# Micro.net
KiCad netlist of a schematic drawn in Altium Designer
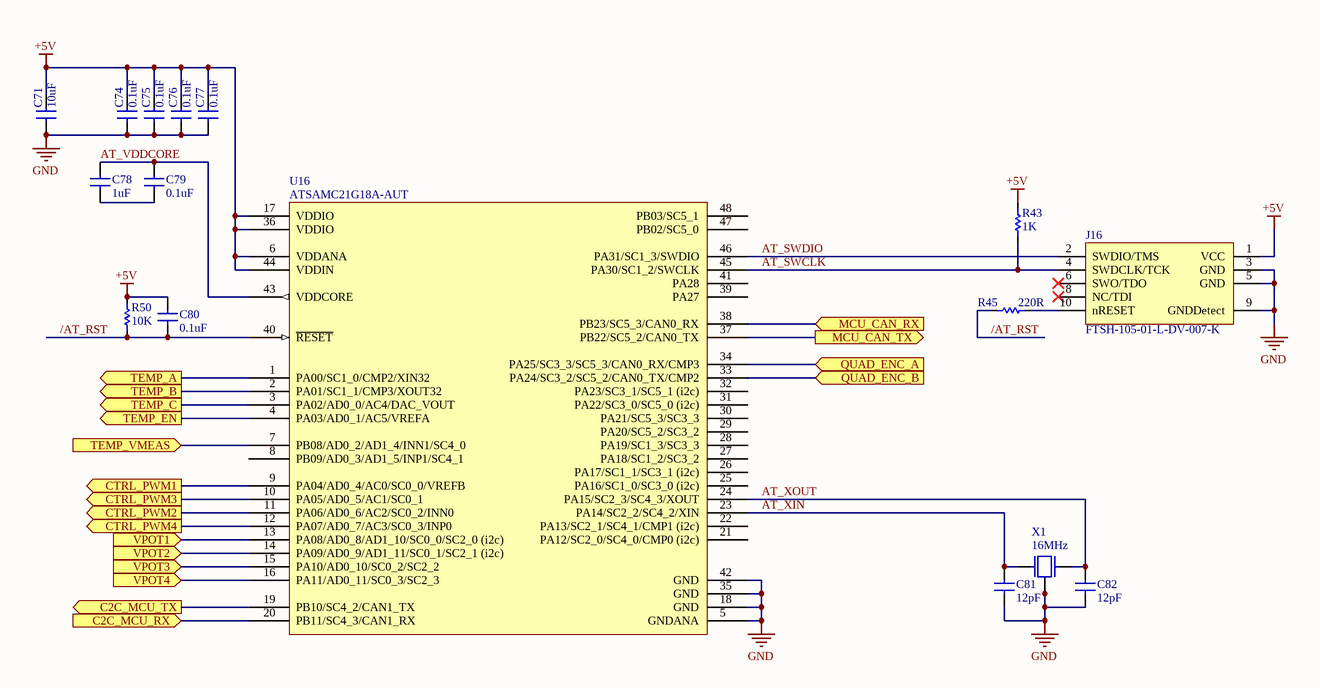
[diagram p0: Micro.SchDoc]

(export (version "E")
  (design (tool "Eeschema 10.0.6"))
  (components
    (comp (ref "C71")
      (value "10uF")
      (footprint "0603_Capacitor")
      (description "CAP CER 10UF 6.3V X5R 0603")
      (fields (field (name "VOLTAGE") "6.3V") (field (name "Comment") "CAP 10uF 6.3V X5R"))
      (libsource (lib "capacitor") (part "C_0603_10uF_6.3V_20%"))
    )
    (comp (ref "C74")
      (value "0.1uF")
      (footprint "0402_CAPACITOR")
      (description "CAP CERM 0.1uF 10% 16V 0402")
      (fields (field (name "VOLTAGE") "16V") (field (name "Comment") "CAP 0.1uF 16V X7R"))
      (libsource (lib "capacitor") (part "C_0402_0.1uF_16V_10%"))
    )
    (comp (ref "C75")
      (value "0.1uF")
      (footprint "0402_CAPACITOR")
      (description "CAP CERM 0.1uF 10% 16V 0402")
      (fields (field (name "VOLTAGE") "16V") (field (name "Comment") "CAP 0.1uF 16V X7R"))
      (libsource (lib "capacitor") (part "C_0402_0.1uF_16V_10%"))
    )
    (comp (ref "C76")
      (value "0.1uF")
      (footprint "0402_CAPACITOR")
      (description "CAP CERM 0.1uF 10% 16V 0402")
      (fields (field (name "VOLTAGE") "16V") (field (name "Comment") "CAP 0.1uF 16V X7R"))
      (libsource (lib "capacitor") (part "C_0402_0.1uF_16V_10%"))
    )
    (comp (ref "C77")
      (value "0.1uF")
      (footprint "0402_CAPACITOR")
      (description "CAP CERM 0.1uF 10% 16V 0402")
      (fields (field (name "VOLTAGE") "16V") (field (name "Comment") "CAP 0.1uF 16V X7R"))
      (libsource (lib "capacitor") (part "C_0402_0.1uF_16V_10%"))
    )
    (comp (ref "C78")
      (value "1uF")
      (footprint "0603_CAPACITOR")
      (description "CAP CERM 1uF 10% 16V 0603")
      (fields
        (field (name "VOLTAGE") "16V")
        (field (name "Comment") "CAP 1uF 16V X7R")
        (field (name "SVP CREATOR") "Spencer Berglund")
      )
      (libsource (lib "capacitor") (part "C_0603_1uF_16V_10%"))
    )
    (comp (ref "C79")
      (value "0.1uF")
      (footprint "0402_CAPACITOR")
      (description "CAP CERM 0.1uF 10% 16V 0402")
      (fields (field (name "VOLTAGE") "16V") (field (name "Comment") "CAP 0.1uF 16V X7R"))
      (libsource (lib "capacitor") (part "C_0402_0.1uF_16V_10%"))
    )
    (comp (ref "C80")
      (value "0.1uF")
      (footprint "0402_CAPACITOR")
      (description "CAP CERM 0.1uF 10% 16V 0402")
      (fields (field (name "VOLTAGE") "16V") (field (name "Comment") "CAP 0.1uF 16V X7R"))
      (libsource (lib "capacitor") (part "C_0402_0.1uF_16V_10%"))
    )
    (comp (ref "C81")
      (value "12pF")
      (footprint "0402_CAPACITOR")
      (fields
        (field (name "VOLTAGE") "50V")
        (field (name "MANUFACTURER") "Samsung")
        (field (name "MANUFACTURER PART NUMBER") "CL05CJB5NNNC")
      )
      (libsource (lib "capacitor") (part "C_0402_generic_C0G/NP0_50V_5%"))
    )
    (comp (ref "C82")
      (value "12pF")
      (footprint "0402_CAPACITOR")
      (fields
        (field (name "VOLTAGE") "50V")
        (field (name "MANUFACTURER") "Samsung")
        (field (name "MANUFACTURER PART NUMBER") "CL05CJB5NNNC")
      )
      (libsource (lib "capacitor") (part "C_0402_generic_C0G/NP0_50V_5%"))
    )
    (comp (ref "J16")
      (value "FTSH-105-01-L-DV-007-K")
      (footprint "J_Cortex_JTAG_SMD")
      (description "CORTEX JTAG DEBUG CONNECTOR")
      (fields (field (name "MANUFACTURER") "Samtec Inc"))
      (libsource (lib "connector") (part "J_Cortex_JTAG_SMD"))
    )
    (comp (ref "R43")
      (value "1K")
      (footprint "0402_Resistor")
      (description "Generic 0402 Resistor (10.2R to 10M)")
      (fields (field (name "TOLERANCE") "±1%") (field (name "MANUFACTURER") "Yageo"))
      (libsource (lib "resistor") (part "R_0402_generic_1%"))
    )
    (comp (ref "R45")
      (value "220R")
      (footprint "0402_Resistor")
      (description "Generic 0402 Resistor (10.2R to 10M)")
      (fields (field (name "TOLERANCE") "±1%") (field (name "MANUFACTURER") "Yageo"))
      (libsource (lib "resistor") (part "R_0402_generic_1%"))
    )
    (comp (ref "R50")
      (value "10K")
      (footprint "0402_Resistor")
      (description "Generic 0402 Resistor (10.2R to 10M)")
      (fields (field (name "TOLERANCE") "±1%") (field (name "MANUFACTURER") "Yageo"))
      (libsource (lib "resistor") (part "R_0402_generic_1%"))
    )
    (comp (ref "U16")
      (value "ATSAMC21G18A-AUT")
      (footprint "TQFP-48")
      (description "ARM® Cortex®-M0+ SAM C21 Microcontroller IC 32-Bit 48MHz 256KB (256K x 8) FLASH 48-TQFP (7x7)")
      (libsource (lib "ic") (part "U_ATSAMC21G18A-AUT"))
    )
    (comp (ref "X1")
      (value "16MHz")
      (footprint "X_TSX-3225")
      (description "16MHz ±10ppm Crystal 9pF 60 Ohms 4-SMD, No Lead")
      (fields
        (field (name "MANUFACTURER") "Epson")
        (field (name "MANUFACTURER PART NUMBER") "TSX-322516.0000MF18X-AC3")
      )
      (libsource (lib "misc") (part "X_TSX-3225_16.0000MF18X"))
    )
  )
  (nets
    (net (code "1") (name "+5V") (class "Default")
      (node (ref "C71") (pin "1") (pinfunction "1_1") (pintype "passive"))
      (node (ref "C74") (pin "1") (pinfunction "1_1") (pintype "passive"))
      (node (ref "C75") (pin "1") (pinfunction "1_1") (pintype "passive"))
      (node (ref "C76") (pin "1") (pinfunction "1_1") (pintype "passive"))
      (node (ref "C77") (pin "1") (pinfunction "1_1") (pintype "passive"))
      (node (ref "C80") (pin "1") (pinfunction "1_1") (pintype "passive"))
      (node (ref "J16") (pin "1") (pinfunction "VCC_1") (pintype "passive"))
      (node (ref "R43") (pin "1") (pinfunction "1_1") (pintype "passive"))
      (node (ref "R50") (pin "1") (pinfunction "1_1") (pintype "passive"))
      (node (ref "U16") (pin "17") (pinfunction "VDDIO_17") (pintype "power_in"))
      (node (ref "U16") (pin "36") (pinfunction "VDDIO_36") (pintype "power_in"))
      (node (ref "U16") (pin "44") (pinfunction "VDDIN_44") (pintype "power_in"))
      (node (ref "U16") (pin "6") (pinfunction "VDDANA_6") (pintype "power_in"))
    )
    (net (code "2") (name "/AT_SWCLK") (class "Default")
      (node (ref "J16") (pin "4") (pinfunction "SWDCLK/TCK_4") (pintype "passive"))
      (node (ref "R43") (pin "2") (pinfunction "2_2") (pintype "passive"))
      (node (ref "U16") (pin "45") (pinfunction "PA30/SC1_2/SWCLK_45") (pintype "passive"))
    )
    (net (code "3") (name "/AT_SWDIO") (class "Default")
      (node (ref "J16") (pin "2") (pinfunction "SWDIO/TMS_2") (pintype "passive"))
      (node (ref "U16") (pin "46") (pinfunction "PA31/SC1_3/SWDIO_46") (pintype "passive"))
    )
    (net (code "4") (name "/AT_VDDCORE") (class "Default")
      (node (ref "C78") (pin "2") (pinfunction "2_2") (pintype "passive"))
      (node (ref "C79") (pin "2") (pinfunction "2_2") (pintype "passive"))
      (node (ref "U16") (pin "43") (pinfunction "VDDCORE_43") (pintype "output"))
    )
    (net (code "5") (name "/AT_XIN") (class "Default")
      (node (ref "C81") (pin "1") (pinfunction "1_1") (pintype "passive"))
      (node (ref "U16") (pin "23") (pinfunction "PA14/SC2_2/SC4_2/XIN_23") (pintype "passive"))
      (node (ref "X1") (pin "1") (pinfunction "1_1") (pintype "passive"))
    )
    (net (code "6") (name "/AT_XOUT") (class "Default")
      (node (ref "C82") (pin "1") (pinfunction "1_1") (pintype "passive"))
      (node (ref "U16") (pin "24") (pinfunction "PA15/SC2_3/SC4_3/XOUT_24") (pintype "passive"))
      (node (ref "X1") (pin "3") (pinfunction "3_3") (pintype "passive"))
    )
    (net (code "7") (name "/C2C_MCU_RX") (class "Default")
      (node (ref "U16") (pin "20") (pinfunction "PB11/SC4_3/CAN1_RX_20") (pintype "passive"))
    )
    (net (code "8") (name "/C2C_MCU_TX") (class "Default")
      (node (ref "U16") (pin "19") (pinfunction "PB10/SC4_2/CAN1_TX_19") (pintype "passive"))
    )
    (net (code "9") (name "/CTRL_PWM1") (class "Default")
      (node (ref "U16") (pin "9") (pinfunction "PA04/AD0_4/AC0/SC0_0/VREFB_9") (pintype "passive"))
    )
    (net (code "10") (name "/CTRL_PWM2") (class "Default")
      (node (ref "U16") (pin "11") (pinfunction "PA06/AD0_6/AC2/SC0_2/INN0_11") (pintype "passive"))
    )
    (net (code "11") (name "/CTRL_PWM3") (class "Default")
      (node (ref "U16") (pin "10") (pinfunction "PA05/AD0_5/AC1/SC0_1_10") (pintype "passive"))
    )
    (net (code "12") (name "/CTRL_PWM4") (class "Default")
      (node (ref "U16") (pin "12") (pinfunction "PA07/AD0_7/AC3/SC0_3/INP0_12") (pintype "passive"))
    )
    (net (code "13") (name "/MCU_CAN_RX") (class "Default")
      (node (ref "U16") (pin "38") (pinfunction "PB23/SC5_3/CAN0_RX_38") (pintype "passive"))
    )
    (net (code "14") (name "/MCU_CAN_TX") (class "Default")
      (node (ref "U16") (pin "37") (pinfunction "PB22/SC5_2/CAN0_TX_37") (pintype "passive"))
    )
    (net (code "15") (name "/QUAD_ENC_A") (class "Default")
      (node (ref "U16") (pin "34") (pinfunction "PA25/SC3_3/SC5_3/CAN0_RX/CMP3_34") (pintype "passive"))
    )
    (net (code "16") (name "/QUAD_ENC_B") (class "Default")
      (node (ref "U16") (pin "33") (pinfunction "PA24/SC3_2/SC5_2/CAN0_TX/CMP2_33") (pintype "passive"))
    )
    (net (code "17") (name "/TEMP_A") (class "Default")
      (node (ref "U16") (pin "1") (pinfunction "PA00/SC1_0/CMP2/XIN32_1") (pintype "passive"))
    )
    (net (code "18") (name "/TEMP_B") (class "Default")
      (node (ref "U16") (pin "2") (pinfunction "PA01/SC1_1/CMP3/XOUT32_2") (pintype "passive"))
    )
    (net (code "19") (name "/TEMP_C") (class "Default")
      (node (ref "U16") (pin "3") (pinfunction "PA02/AD0_0/AC4/DAC_VOUT_3") (pintype "passive"))
    )
    (net (code "20") (name "/TEMP_EN") (class "Default")
      (node (ref "U16") (pin "4") (pinfunction "PA03/AD0_1/AC5/VREFA_4") (pintype "passive"))
    )
    (net (code "21") (name "/TEMP_VMEAS") (class "Default")
      (node (ref "U16") (pin "7") (pinfunction "PB08/AD0_2/AD1_4/INN1/SC4_0_7") (pintype "passive"))
    )
    (net (code "22") (name "/VPOT1") (class "Default")
      (node (ref "U16") (pin "13") (pinfunction "PA08/AD0_8/AD1_10/SC0_0/SC2_0_(i2c)_13") (pintype "passive"))
    )
    (net (code "23") (name "/VPOT2") (class "Default")
      (node (ref "U16") (pin "14") (pinfunction "PA09/AD0_9/AD1_11/SC0_1/SC2_1_(i2c)_14") (pintype "passive"))
    )
    (net (code "24") (name "/VPOT3") (class "Default")
      (node (ref "U16") (pin "15") (pinfunction "PA10/AD0_10/SC0_2/SC2_2_15") (pintype "passive"))
    )
    (net (code "25") (name "/VPOT4") (class "Default")
      (node (ref "U16") (pin "16") (pinfunction "PA11/AD0_11/SC0_3/SC2_3_16") (pintype "passive"))
    )
    (net (code "26") (name "/{slash}AT_RST") (class "Default")
      (node (ref "C80") (pin "2") (pinfunction "2_2") (pintype "passive"))
      (node (ref "R45") (pin "1") (pinfunction "1_1") (pintype "passive"))
      (node (ref "R50") (pin "2") (pinfunction "2_2") (pintype "passive"))
      (node (ref "U16") (pin "40") (pinfunction "~{RESET}_40") (pintype "input"))
    )
    (net (code "27") (name "GND") (class "Default")
      (node (ref "C71") (pin "2") (pinfunction "2_2") (pintype "passive"))
      (node (ref "C74") (pin "2") (pinfunction "2_2") (pintype "passive"))
      (node (ref "C75") (pin "2") (pinfunction "2_2") (pintype "passive"))
      (node (ref "C76") (pin "2") (pinfunction "2_2") (pintype "passive"))
      (node (ref "C77") (pin "2") (pinfunction "2_2") (pintype "passive"))
      (node (ref "C81") (pin "2") (pinfunction "2_2") (pintype "passive"))
      (node (ref "C82") (pin "2") (pinfunction "2_2") (pintype "passive"))
      (node (ref "J16") (pin "3") (pinfunction "GND_3") (pintype "passive"))
      (node (ref "J16") (pin "5") (pinfunction "GND_5") (pintype "passive"))
      (node (ref "J16") (pin "9") (pinfunction "GNDDetect_9") (pintype "passive"))
      (node (ref "U16") (pin "18") (pinfunction "GND_18") (pintype "power_in"))
      (node (ref "U16") (pin "35") (pinfunction "GND_35") (pintype "power_in"))
      (node (ref "U16") (pin "42") (pinfunction "GND_42") (pintype "power_in"))
      (node (ref "U16") (pin "5") (pinfunction "GNDANA_5") (pintype "power_in"))
      (node (ref "X1") (pin "2") (pinfunction "2_2") (pintype "passive"))
      (node (ref "X1") (pin "4") (pinfunction "4_4") (pintype "passive"))
    )
    (net (code "28") (name "Net-(C78-Pad1)") (class "Default")
      (node (ref "C78") (pin "1") (pinfunction "1_1") (pintype "passive"))
      (node (ref "C79") (pin "1") (pinfunction "1_1") (pintype "passive"))
    )
    (net (code "29") (name "Net-(J16-nRESET)") (class "Default")
      (node (ref "J16") (pin "10") (pinfunction "nRESET_10") (pintype "passive"))
      (node (ref "R45") (pin "2") (pinfunction "2_2") (pintype "passive"))
    )
    (net (code "30") (name "unconnected-(J16-NC{slash}TDI-Pad8)") (class "Default")
      (node (ref "J16") (pin "8") (pinfunction "NC/TDI_8") (pintype "passive+no_connect"))
    )
    (net (code "31") (name "unconnected-(J16-SWO{slash}TDO-Pad6)") (class "Default")
      (node (ref "J16") (pin "6") (pinfunction "SWO/TDO_6") (pintype "passive+no_connect"))
    )
    (net (code "32") (name "unconnected-(U16-PA12{slash}SC2_0{slash}SC4_0{slash}CMP0_(i2c)-Pad21)") (class "Default")
      (node (ref "U16") (pin "21") (pinfunction "PA12/SC2_0/SC4_0/CMP0_(i2c)_21") (pintype "passive"))
    )
    (net (code "33") (name "unconnected-(U16-PA13{slash}SC2_1{slash}SC4_1{slash}CMP1_(i2c)-Pad22)") (class "Default")
      (node (ref "U16") (pin "22") (pinfunction "PA13/SC2_1/SC4_1/CMP1_(i2c)_22") (pintype "passive"))
    )
    (net (code "34") (name "unconnected-(U16-PA16{slash}SC1_0{slash}SC3_0_(i2c)-Pad25)") (class "Default")
      (node (ref "U16") (pin "25") (pinfunction "PA16/SC1_0/SC3_0_(i2c)_25") (pintype "passive"))
    )
    (net (code "35") (name "unconnected-(U16-PA17{slash}SC1_1{slash}SC3_1_(i2c)-Pad26)") (class "Default")
      (node (ref "U16") (pin "26") (pinfunction "PA17/SC1_1/SC3_1_(i2c)_26") (pintype "passive"))
    )
    (net (code "36") (name "unconnected-(U16-PA18{slash}SC1_2{slash}SC3_2-Pad27)") (class "Default")
      (node (ref "U16") (pin "27") (pinfunction "PA18/SC1_2/SC3_2_27") (pintype "passive"))
    )
    (net (code "37") (name "unconnected-(U16-PA19{slash}SC1_3{slash}SC3_3-Pad28)") (class "Default")
      (node (ref "U16") (pin "28") (pinfunction "PA19/SC1_3/SC3_3_28") (pintype "passive"))
    )
    (net (code "38") (name "unconnected-(U16-PA20{slash}SC5_2{slash}SC3_2-Pad29)") (class "Default")
      (node (ref "U16") (pin "29") (pinfunction "PA20/SC5_2/SC3_2_29") (pintype "passive"))
    )
    (net (code "39") (name "unconnected-(U16-PA21{slash}SC5_3{slash}SC3_3-Pad30)") (class "Default")
      (node (ref "U16") (pin "30") (pinfunction "PA21/SC5_3/SC3_3_30") (pintype "passive"))
    )
    (net (code "40") (name "unconnected-(U16-PA22{slash}SC3_0{slash}SC5_0_(i2c)-Pad31)") (class "Default")
      (node (ref "U16") (pin "31") (pinfunction "PA22/SC3_0/SC5_0_(i2c)_31") (pintype "passive"))
    )
    (net (code "41") (name "unconnected-(U16-PA23{slash}SC3_1{slash}SC5_1_(i2c)-Pad32)") (class "Default")
      (node (ref "U16") (pin "32") (pinfunction "PA23/SC3_1/SC5_1_(i2c)_32") (pintype "passive"))
    )
    (net (code "42") (name "unconnected-(U16-PA27-Pad39)") (class "Default")
      (node (ref "U16") (pin "39") (pinfunction "PA27_39") (pintype "passive"))
    )
    (net (code "43") (name "unconnected-(U16-PA28-Pad41)") (class "Default")
      (node (ref "U16") (pin "41") (pinfunction "PA28_41") (pintype "passive"))
    )
    (net (code "44") (name "unconnected-(U16-PB02{slash}SC5_0-Pad47)") (class "Default")
      (node (ref "U16") (pin "47") (pinfunction "PB02/SC5_0_47") (pintype "passive"))
    )
    (net (code "45") (name "unconnected-(U16-PB03{slash}SC5_1-Pad48)") (class "Default")
      (node (ref "U16") (pin "48") (pinfunction "PB03/SC5_1_48") (pintype "passive"))
    )
    (net (code "46") (name "unconnected-(U16-PB09{slash}AD0_3{slash}AD1_5{slash}INP1{slash}SC4_1-Pad8)") (class "Default")
      (node (ref "U16") (pin "8") (pinfunction "PB09/AD0_3/AD1_5/INP1/SC4_1_8") (pintype "passive"))
    )
  )
)
